# DepthSensor.net
KiCad netlist of a schematic drawn in Altium Designer
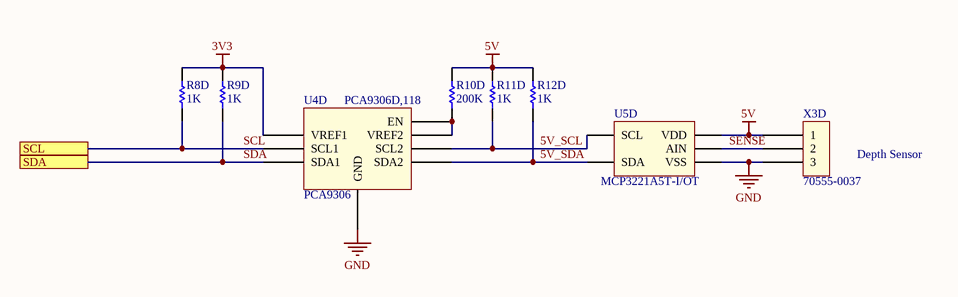
[diagram p0: DepthSensor.SchDoc]

(export (version "E")
  (design (tool "Eeschema 10.0.6"))
  (components
    (comp (ref "R8D")
      (value "1K")
      (footprint "R0805")
      (description "Resistor")
      (fields (field (name "TOLERANCE") "5%"))
      (libsource (lib "URC_Lib") (part "Res"))
    )
    (comp (ref "R9D")
      (value "1K")
      (footprint "R0805")
      (description "Resistor")
      (fields (field (name "TOLERANCE") "5%"))
      (libsource (lib "URC_Lib") (part "Res"))
    )
    (comp (ref "R10D")
      (value "200K")
      (footprint "R0805")
      (description "Resistor")
      (fields (field (name "TOLERANCE") "5%"))
      (libsource (lib "URC_Lib") (part "Res"))
    )
    (comp (ref "R11D")
      (value "1K")
      (footprint "R0805")
      (description "Resistor")
      (fields (field (name "TOLERANCE") "5%"))
      (libsource (lib "URC_Lib") (part "Res"))
    )
    (comp (ref "R12D")
      (value "1K")
      (footprint "R0805")
      (description "Resistor")
      (fields (field (name "TOLERANCE") "5%"))
      (libsource (lib "URC_Lib") (part "Res"))
    )
    (comp (ref "U4D")
      (value "PCA9306")
      (footprint "PCA9306-SO8")
      (description "PCA9306, Bidirectional level translator")
      (fields (field (name "MANUFACTURER") "NXP") (field (name "MANUFACTURER PART NUMBER") "PCA9306D,118"))
      (libsource (lib "URC") (part "PCA9306"))
    )
    (comp (ref "U5D")
      (value "~")
      (footprint "MCP3221-SOT23-5")
      (description "MCP3221, 12 bit ADC, I2C")
      (fields
        (field (name "MANUFACTURER") "MICROCHIP")
        (field (name "MANUFACTURER PART NUMBER") "MCP3221A5T-I/OT")
      )
      (libsource (lib "URC") (part "MCP3221"))
    )
    (comp (ref "X3D")
      (value "70555-0037")
      (footprint "70555-0037")
      (description "Molex, C-Grid SL 70555, 3 Pin")
      (fields (field (name "MANUFACTURER") "MOLEX"))
      (libsource (lib "URC") (part "70555-0037"))
    )
  )
  (nets
    (net (code "1") (name "/5V_SCL") (class "Default")
      (node (ref "R11D") (pin "1") (pinfunction "1_1") (pintype "passive"))
      (node (ref "U4D") (pin "SCL2") (pinfunction "SCL2_SCL2") (pintype "passive"))
      (node (ref "U5D") (pin "SCL") (pinfunction "SCL_SCL") (pintype "passive"))
    )
    (net (code "2") (name "/5V_SDA") (class "Default")
      (node (ref "R12D") (pin "1") (pinfunction "1_1") (pintype "passive"))
      (node (ref "U4D") (pin "SDA2") (pinfunction "SDA2_SDA2") (pintype "passive"))
      (node (ref "U5D") (pin "SDA") (pinfunction "SDA_SDA") (pintype "passive"))
    )
    (net (code "3") (name "/SCL") (class "Default")
      (node (ref "R8D") (pin "1") (pinfunction "1_1") (pintype "passive"))
      (node (ref "U4D") (pin "SCL1") (pinfunction "SCL1_SCL1") (pintype "passive"))
    )
    (net (code "4") (name "/SDA") (class "Default")
      (node (ref "R9D") (pin "1") (pinfunction "1_1") (pintype "passive"))
      (node (ref "U4D") (pin "SDA1") (pinfunction "SDA1_SDA1") (pintype "passive"))
    )
    (net (code "5") (name "/SENSE") (class "Default")
      (node (ref "U5D") (pin "AIN") (pinfunction "AIN_AIN") (pintype "passive"))
      (node (ref "X3D") (pin "2") (pinfunction "2_2") (pintype "passive"))
    )
    (net (code "6") (name "3V3") (class "Default")
      (node (ref "R8D") (pin "2") (pinfunction "2_2") (pintype "passive"))
      (node (ref "R9D") (pin "2") (pinfunction "2_2") (pintype "passive"))
      (node (ref "U4D") (pin "VREF1") (pinfunction "VREF1_VREF1") (pintype "passive"))
    )
    (net (code "7") (name "5V") (class "Default")
      (node (ref "R10D") (pin "2") (pinfunction "2_2") (pintype "passive"))
      (node (ref "R11D") (pin "2") (pinfunction "2_2") (pintype "passive"))
      (node (ref "R12D") (pin "2") (pinfunction "2_2") (pintype "passive"))
      (node (ref "U5D") (pin "VDD") (pinfunction "VDD_VDD") (pintype "passive"))
      (node (ref "X3D") (pin "1") (pinfunction "1_1") (pintype "passive"))
    )
    (net (code "8") (name "GND") (class "Default")
      (node (ref "U4D") (pin "GND") (pinfunction "GND_GND") (pintype "passive"))
      (node (ref "U5D") (pin "VSS") (pinfunction "VSS_VSS") (pintype "passive"))
      (node (ref "X3D") (pin "3") (pinfunction "3_3") (pintype "passive"))
    )
    (net (code "9") (name "Net-(R10D-Pad1)") (class "Default")
      (node (ref "R10D") (pin "1") (pinfunction "1_1") (pintype "passive"))
      (node (ref "U4D") (pin "EN") (pinfunction "EN_EN") (pintype "passive"))
      (node (ref "U4D") (pin "VREF2") (pinfunction "VREF2_VREF2") (pintype "passive"))
    )
  )
)
